# fet_overdrive_v30.net
KiCad netlist of a schematic drawn in EAGLE
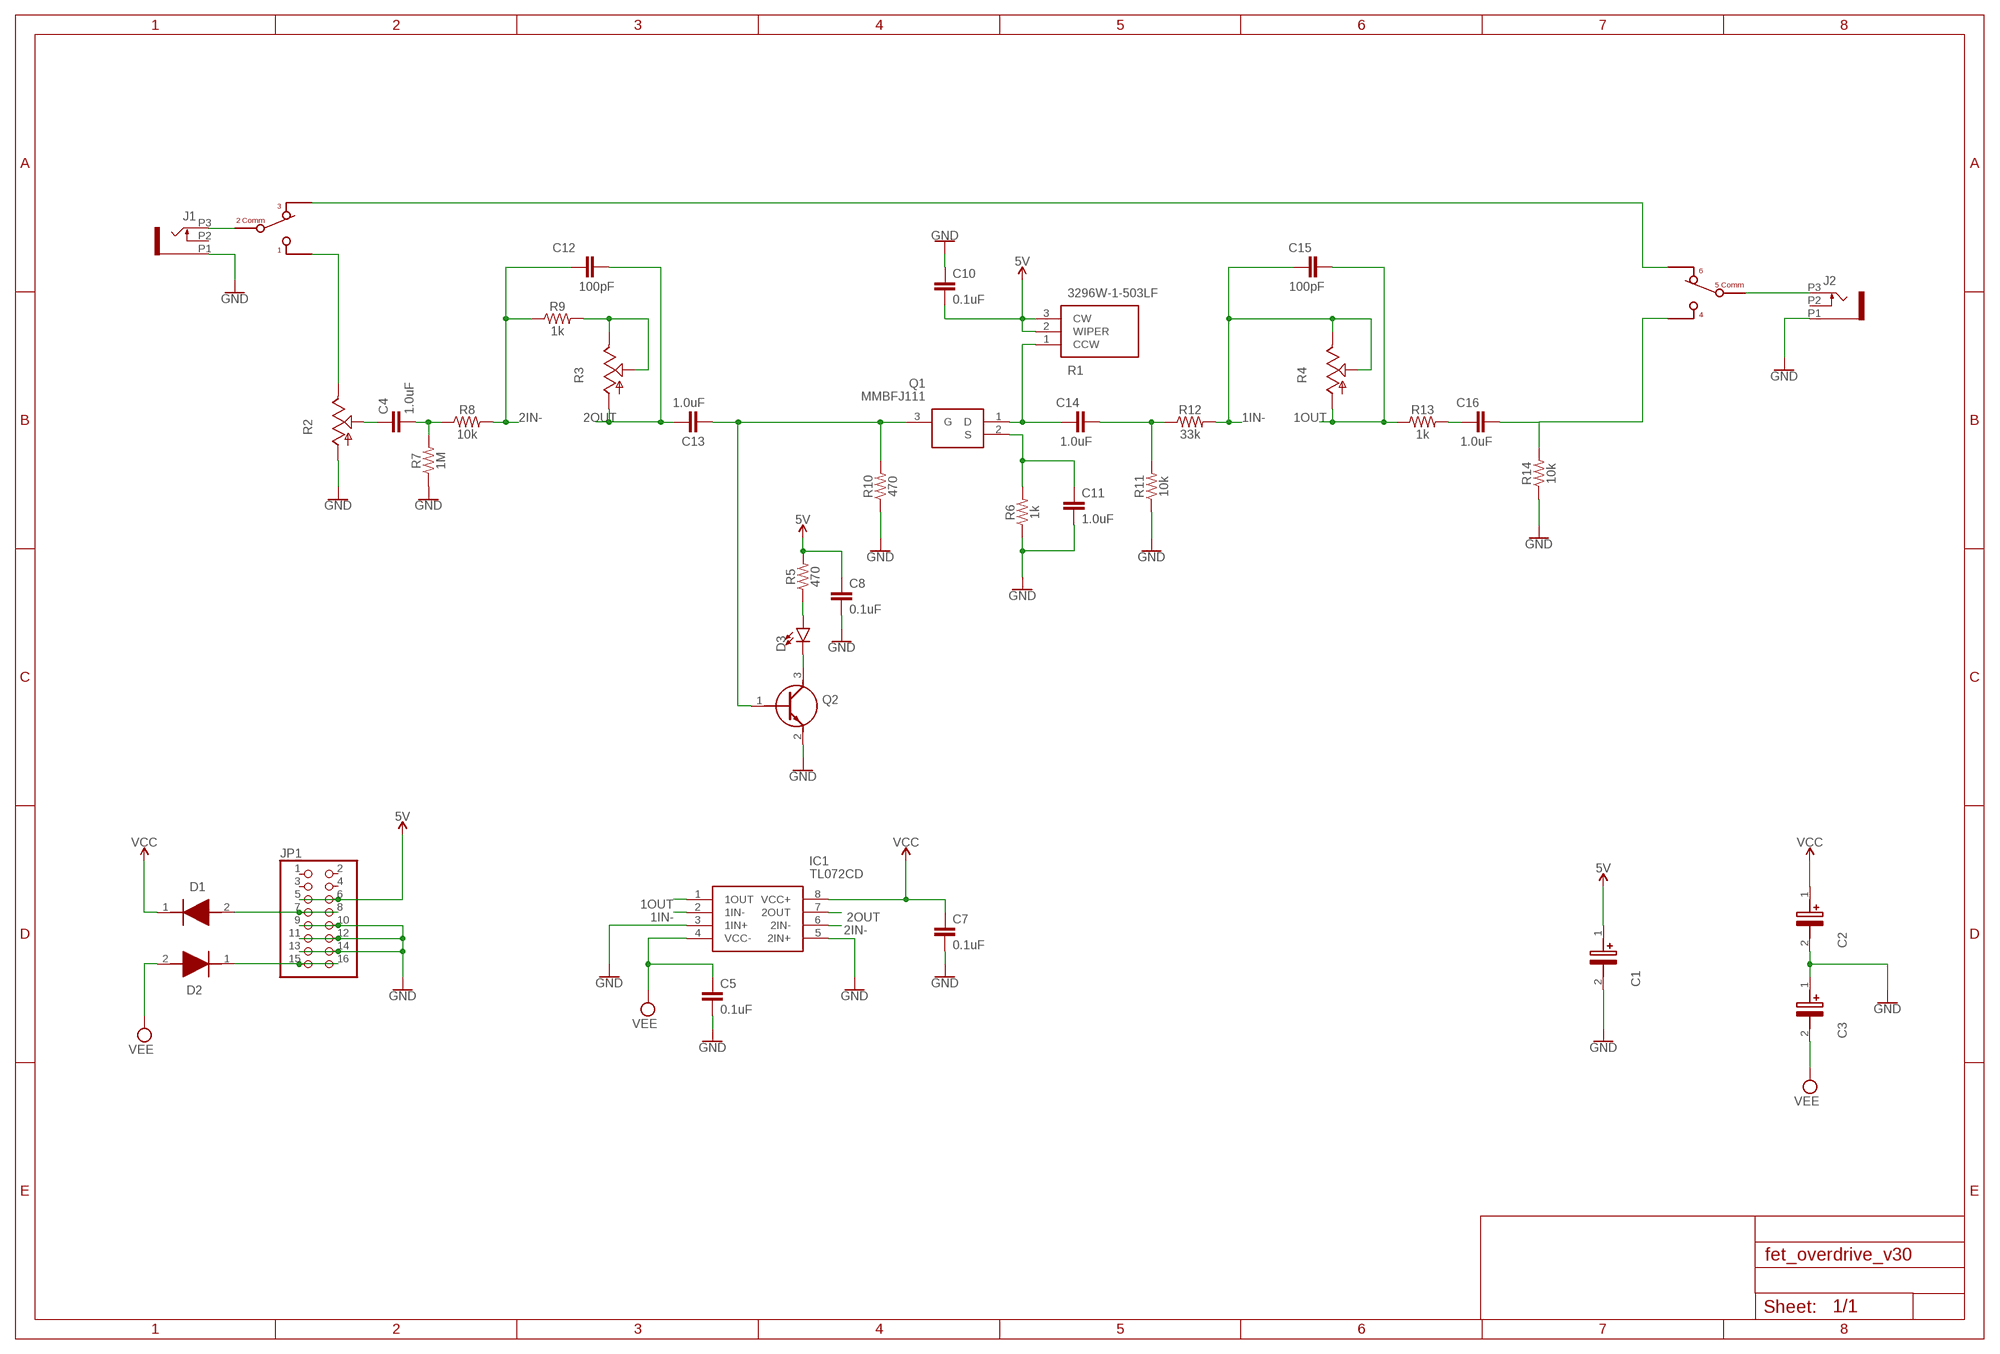
[diagram p0: schematic, sheet 1]

(export (version "E")
  (design (tool "Eeschema 10.0.6"))
  (components
    (comp (ref "C1")
      (value "EEE-FP1E220AR")
      (footprint "eagle-import:EEE0GA101SR")
      (fields (field (name "MOUSER_PART_NUMBER") "667-EEE-FP1E220AR"))
      (libsource (lib "eagle-import") (part "EEE-FP1E220AR"))
    )
    (comp (ref "C2")
      (value "EEE-FK1V470P")
      (footprint "eagle-import:EEE1AA101SP")
      (fields (field (name "MOUSER_PART_NUMBER") "667-EEE-FK1V470P"))
      (libsource (lib "eagle-import") (part "EEE-FK1V470P"))
    )
    (comp (ref "C3")
      (value "EEE-FK1V470P")
      (footprint "eagle-import:EEE1AA101SP")
      (fields (field (name "MOUSER_PART_NUMBER") "667-EEE-FK1V470P"))
      (libsource (lib "eagle-import") (part "EEE-FK1V470P"))
    )
    (comp (ref "C4")
      (value "1.0uF")
      (footprint "eagle-import:0603")
      (libsource (lib "eagle-import") (part "1.0UF-0603-16V-10%"))
    )
    (comp (ref "C5")
      (value "0.1uF")
      (footprint "eagle-import:0603")
      (libsource (lib "eagle-import") (part "0.1UF-0603-25V-5%"))
    )
    (comp (ref "C7")
      (value "0.1uF")
      (footprint "eagle-import:0603")
      (libsource (lib "eagle-import") (part "0.1UF-0603-25V-5%"))
    )
    (comp (ref "C8")
      (value "0.1uF")
      (footprint "eagle-import:0603")
      (libsource (lib "eagle-import") (part "0.1UF-0603-25V-5%"))
    )
    (comp (ref "C10")
      (value "0.1uF")
      (footprint "eagle-import:0603")
      (libsource (lib "eagle-import") (part "0.1UF-0603-25V-5%"))
    )
    (comp (ref "C11")
      (value "1.0uF")
      (footprint "eagle-import:0603")
      (libsource (lib "eagle-import") (part "1.0UF-0603-16V-10%"))
    )
    (comp (ref "C12")
      (value "100pF")
      (footprint "eagle-import:0603")
      (libsource (lib "eagle-import") (part "100PF-0603-50V-5%"))
    )
    (comp (ref "C13")
      (value "1.0uF")
      (footprint "eagle-import:0603")
      (libsource (lib "eagle-import") (part "1.0UF-0603-16V-10%"))
    )
    (comp (ref "C14")
      (value "1.0uF")
      (footprint "eagle-import:0603")
      (libsource (lib "eagle-import") (part "1.0UF-0603-16V-10%"))
    )
    (comp (ref "C15")
      (value "100pF")
      (footprint "eagle-import:0603")
      (libsource (lib "eagle-import") (part "100PF-0603-50V-5%"))
    )
    (comp (ref "C16")
      (value "1.0uF")
      (footprint "eagle-import:0603")
      (libsource (lib "eagle-import") (part "1.0UF-0603-16V-10%"))
    )
    (comp (ref "D1")
      (value "1N5819HW-7-F")
      (footprint "eagle-import:SOD3716X145N")
      (fields (field (name "MOUSER_PART_NUMBER") "621-1N5819HW-F"))
      (libsource (lib "eagle-import") (part "1N5819HW-7-F"))
    )
    (comp (ref "D2")
      (value "1N5819HW-7-F")
      (footprint "eagle-import:SOD3716X145N")
      (fields (field (name "MOUSER_PART_NUMBER") "621-1N5819HW-F"))
      (libsource (lib "eagle-import") (part "1N5819HW-7-F"))
    )
    (comp (ref "D3")
      (value "LED3MM")
      (footprint "eagle-import:LED_3MM")
      (libsource (lib "eagle-import") (part "LED3MM"))
    )
    (comp (ref "IC1")
      (value "TL072CD")
      (footprint "eagle-import:SOIC127P600X175-8N")
      (fields (field (name "MOUSER_PART_NUMBER") "595-TL072CD"))
      (libsource (lib "eagle-import") (part "TL072CD"))
    )
    (comp (ref "J1")
      (value "PJ301_THONKICONN6")
      (footprint "eagle-import:WQP_PJ_301M6")
      (libsource (lib "eagle-import") (part "PJ301_THONKICONN6"))
    )
    (comp (ref "J2")
      (value "PJ301_THONKICONN6")
      (footprint "eagle-import:WQP_PJ_301M6")
      (libsource (lib "eagle-import") (part "PJ301_THONKICONN6"))
    )
    (comp (ref "JP1")
      (value "PINHD-2X8")
      (footprint "eagle-import:2X08")
      (libsource (lib "eagle-import") (part "PINHD-2X8"))
    )
    (comp (ref "Q1")
      (value "MMBFJ111")
      (footprint "eagle-import:SOT96P237X111-3N")
      (fields (field (name "MOUSER_PART_NUMBER") "512-MMBFJ111"))
      (libsource (lib "eagle-import") (part "MMBFJ111"))
    )
    (comp (ref "Q2")
      (value "SMMBT3904LT1G")
      (footprint "eagle-import:SOT96P237X111-3N")
      (fields (field (name "MOUSER_PART_NUMBER") "863-SMMBT3904LT1G"))
      (libsource (lib "eagle-import") (part "SMMBT3904LT1G"))
    )
    (comp (ref "R1")
      (value "3296W-1-503LF")
      (footprint "eagle-import:3296W-1")
      (fields (field (name "MOUSER_PART_NUMBER") "652-3296W-1-503LF"))
      (libsource (lib "eagle-import") (part "3296W-1-503LF"))
    )
    (comp (ref "R2")
      (value "POT_USVERTICAL_PS")
      (footprint "eagle-import:ALPS_POT_VERTICAL_PS")
      (libsource (lib "eagle-import") (part "POT_USVERTICAL_PS"))
    )
    (comp (ref "R3")
      (value "POT_USVERTICAL_PS")
      (footprint "eagle-import:ALPS_POT_VERTICAL_PS")
      (libsource (lib "eagle-import") (part "POT_USVERTICAL_PS"))
    )
    (comp (ref "R4")
      (value "POT_USVERTICAL_PS")
      (footprint "eagle-import:ALPS_POT_VERTICAL_PS")
      (libsource (lib "eagle-import") (part "POT_USVERTICAL_PS"))
    )
    (comp (ref "R5")
      (value "470")
      (footprint "eagle-import:0603")
      (libsource (lib "eagle-import") (part "470OHM-0603-1/10W-1%"))
    )
    (comp (ref "R6")
      (value "1k")
      (footprint "eagle-import:0603")
      (libsource (lib "eagle-import") (part "1KOHM-0603-1/10W-1%"))
    )
    (comp (ref "R7")
      (value "1M")
      (footprint "eagle-import:0603")
      (libsource (lib "eagle-import") (part "1MOHM-0603-1/4W-5%"))
    )
    (comp (ref "R8")
      (value "10k")
      (footprint "eagle-import:0603")
      (libsource (lib "eagle-import") (part "10KOHM-0603-1/10W-1%"))
    )
    (comp (ref "R9")
      (value "1k")
      (footprint "eagle-import:0603")
      (libsource (lib "eagle-import") (part "1KOHM-0603-1/10W-1%"))
    )
    (comp (ref "R10")
      (value "470")
      (footprint "eagle-import:0603")
      (libsource (lib "eagle-import") (part "470OHM-0603-1/10W-1%"))
    )
    (comp (ref "R11")
      (value "10k")
      (footprint "eagle-import:0603")
      (libsource (lib "eagle-import") (part "10KOHM-0603-1/10W-1%"))
    )
    (comp (ref "R12")
      (value "33k")
      (footprint "eagle-import:0603")
      (libsource (lib "eagle-import") (part "33KOHM-0603-1/10W-1%"))
    )
    (comp (ref "R13")
      (value "1k")
      (footprint "eagle-import:0603")
      (libsource (lib "eagle-import") (part "1KOHM-0603-1/10W-1%"))
    )
    (comp (ref "R14")
      (value "10k")
      (footprint "eagle-import:0603")
      (libsource (lib "eagle-import") (part "10KOHM-0603-1/10W-1%"))
    )
    (comp (ref "U$1")
      (value "DAILYWELL-DPDT")
      (footprint "eagle-import:DAILYWELL-DPDT")
      (libsource (lib "eagle-import") (part "DAILYWELL-DPDT"))
    )
  )
  (nets
    (net (code "1") (name "/1IN-") (class "Default")
      (node (ref "C15") (pin "1") (pinfunction "1_1") (pintype "passive"))
      (node (ref "IC1") (pin "2") (pinfunction "1IN-_2") (pintype "bidirectional"))
      (node (ref "R12") (pin "2") (pinfunction "2_2") (pintype "passive"))
      (node (ref "R4") (pin "P$1") (pinfunction "E_P$1") (pintype "passive"))
      (node (ref "R4") (pin "P$2") (pinfunction "S_P$2") (pintype "passive"))
    )
    (net (code "2") (name "/1OUT") (class "Default")
      (node (ref "C15") (pin "2") (pinfunction "2_2") (pintype "passive"))
      (node (ref "IC1") (pin "1") (pinfunction "1OUT_1") (pintype "bidirectional"))
      (node (ref "R13") (pin "1") (pinfunction "1_1") (pintype "passive"))
      (node (ref "R4") (pin "P$3") (pinfunction "A_P$3") (pintype "passive"))
    )
    (net (code "3") (name "/2IN-") (class "Default")
      (node (ref "C12") (pin "1") (pinfunction "1_1") (pintype "passive"))
      (node (ref "IC1") (pin "6") (pinfunction "2IN-_6") (pintype "bidirectional"))
      (node (ref "R8") (pin "2") (pinfunction "2_2") (pintype "passive"))
      (node (ref "R9") (pin "1") (pinfunction "1_1") (pintype "passive"))
    )
    (net (code "4") (name "/2OUT") (class "Default")
      (node (ref "C12") (pin "2") (pinfunction "2_2") (pintype "passive"))
      (node (ref "C13") (pin "1") (pinfunction "1_1") (pintype "passive"))
      (node (ref "IC1") (pin "7") (pinfunction "2OUT_7") (pintype "bidirectional"))
      (node (ref "R3") (pin "P$3") (pinfunction "A_P$3") (pintype "passive"))
    )
    (net (code "5") (name "5V") (class "Default")
      (node (ref "C1") (pin "1") (pinfunction "+_1") (pintype "bidirectional"))
      (node (ref "C10") (pin "2") (pinfunction "2_2") (pintype "passive"))
      (node (ref "C8") (pin "1") (pinfunction "1_1") (pintype "passive"))
      (node (ref "JP1") (pin "5") (pinfunction "5_5") (pintype "passive"))
      (node (ref "JP1") (pin "6") (pinfunction "6_6") (pintype "passive"))
      (node (ref "R1") (pin "2") (pinfunction "WIPER_2") (pintype "bidirectional"))
      (node (ref "R1") (pin "3") (pinfunction "CW_3") (pintype "bidirectional"))
      (node (ref "R5") (pin "2") (pinfunction "2_2") (pintype "passive"))
    )
    (net (code "6") (name "GND") (class "Default")
      (node (ref "C1") (pin "2") (pinfunction "-_2") (pintype "bidirectional"))
      (node (ref "C10") (pin "1") (pinfunction "1_1") (pintype "passive"))
      (node (ref "C11") (pin "2") (pinfunction "2_2") (pintype "passive"))
      (node (ref "C2") (pin "2") (pinfunction "-_2") (pintype "bidirectional"))
      (node (ref "C3") (pin "1") (pinfunction "+_1") (pintype "bidirectional"))
      (node (ref "C5") (pin "2") (pinfunction "2_2") (pintype "passive"))
      (node (ref "C7") (pin "2") (pinfunction "2_2") (pintype "passive"))
      (node (ref "C8") (pin "2") (pinfunction "2_2") (pintype "passive"))
      (node (ref "IC1") (pin "3") (pinfunction "1IN+_3") (pintype "bidirectional"))
      (node (ref "IC1") (pin "5") (pinfunction "2IN+_5") (pintype "bidirectional"))
      (node (ref "J1") (pin "P1") (pinfunction "1_P1") (pintype "passive"))
      (node (ref "J2") (pin "P1") (pinfunction "1_P1") (pintype "passive"))
      (node (ref "JP1") (pin "10") (pinfunction "10_10") (pintype "passive"))
      (node (ref "JP1") (pin "11") (pinfunction "11_11") (pintype "passive"))
      (node (ref "JP1") (pin "12") (pinfunction "12_12") (pintype "passive"))
      (node (ref "JP1") (pin "13") (pinfunction "13_13") (pintype "passive"))
      (node (ref "JP1") (pin "14") (pinfunction "14_14") (pintype "passive"))
      (node (ref "JP1") (pin "9") (pinfunction "9_9") (pintype "passive"))
      (node (ref "Q2") (pin "2") (pinfunction "E_2") (pintype "bidirectional"))
      (node (ref "R10") (pin "1") (pinfunction "1_1") (pintype "passive"))
      (node (ref "R11") (pin "1") (pinfunction "1_1") (pintype "passive"))
      (node (ref "R14") (pin "1") (pinfunction "1_1") (pintype "passive"))
      (node (ref "R2") (pin "P$3") (pinfunction "A_P$3") (pintype "passive"))
      (node (ref "R6") (pin "1") (pinfunction "1_1") (pintype "passive"))
      (node (ref "R7") (pin "1") (pinfunction "1_1") (pintype "passive"))
    )
    (net (code "7") (name "Net-(C4-Pad2)") (class "Default")
      (node (ref "C4") (pin "2") (pinfunction "2_2") (pintype "passive"))
      (node (ref "R7") (pin "2") (pinfunction "2_2") (pintype "passive"))
      (node (ref "R8") (pin "1") (pinfunction "1_1") (pintype "passive"))
    )
    (net (code "8") (name "Net-(C14-Pad2)") (class "Default")
      (node (ref "C14") (pin "2") (pinfunction "2_2") (pintype "passive"))
      (node (ref "R11") (pin "2") (pinfunction "2_2") (pintype "passive"))
      (node (ref "R12") (pin "1") (pinfunction "1_1") (pintype "passive"))
    )
    (net (code "9") (name "Net-(C16-Pad1)") (class "Default")
      (node (ref "C16") (pin "1") (pinfunction "1_1") (pintype "passive"))
      (node (ref "R13") (pin "2") (pinfunction "2_2") (pintype "passive"))
    )
    (net (code "10") (name "Net-(D1-A)") (class "Default")
      (node (ref "D1") (pin "2") (pinfunction "A_2") (pintype "bidirectional"))
      (node (ref "JP1") (pin "7") (pinfunction "7_7") (pintype "passive"))
      (node (ref "JP1") (pin "8") (pinfunction "8_8") (pintype "passive"))
    )
    (net (code "11") (name "Net-(D2-K)") (class "Default")
      (node (ref "D2") (pin "1") (pinfunction "K_1") (pintype "bidirectional"))
      (node (ref "JP1") (pin "15") (pinfunction "15_15") (pintype "passive"))
      (node (ref "JP1") (pin "16") (pinfunction "16_16") (pintype "passive"))
    )
    (net (code "12") (name "Net-(D3-C)") (class "Default")
      (node (ref "D3") (pin "K") (pinfunction "C_K") (pintype "passive"))
      (node (ref "Q2") (pin "3") (pinfunction "C_3") (pintype "bidirectional"))
    )
    (net (code "13") (name "Net-(D3-PadA)") (class "Default")
      (node (ref "D3") (pin "A") (pinfunction "A_A") (pintype "passive"))
      (node (ref "R5") (pin "1") (pinfunction "1_1") (pintype "passive"))
    )
    (net (code "14") (name "Net-(J1-3)") (class "Default")
      (node (ref "J1") (pin "P3") (pinfunction "3_P3") (pintype "passive"))
      (node (ref "U$1") (pin "P$2") (pinfunction "P$2_P$2") (pintype "bidirectional"))
    )
    (net (code "15") (name "Net-(J2-3)") (class "Default")
      (node (ref "J2") (pin "P3") (pinfunction "3_P3") (pintype "passive"))
      (node (ref "U$1") (pin "P$5") (pinfunction "P$2_P$5") (pintype "bidirectional"))
    )
    (net (code "16") (name "Net-(Q1-D)") (class "Default")
      (node (ref "C14") (pin "1") (pinfunction "1_1") (pintype "passive"))
      (node (ref "Q1") (pin "1") (pinfunction "D_1") (pintype "bidirectional"))
      (node (ref "R1") (pin "1") (pinfunction "CCW_1") (pintype "bidirectional"))
    )
    (net (code "17") (name "Net-(Q1-G)") (class "Default")
      (node (ref "C13") (pin "2") (pinfunction "2_2") (pintype "passive"))
      (node (ref "Q1") (pin "3") (pinfunction "G_3") (pintype "bidirectional"))
      (node (ref "Q2") (pin "1") (pinfunction "B_1") (pintype "bidirectional"))
      (node (ref "R10") (pin "2") (pinfunction "2_2") (pintype "passive"))
    )
    (net (code "18") (name "Net-(Q1-S)") (class "Default")
      (node (ref "C11") (pin "1") (pinfunction "1_1") (pintype "passive"))
      (node (ref "Q1") (pin "2") (pinfunction "S_2") (pintype "bidirectional"))
      (node (ref "R6") (pin "2") (pinfunction "2_2") (pintype "passive"))
    )
    (net (code "19") (name "Net-(R2-E)") (class "Default")
      (node (ref "R2") (pin "P$1") (pinfunction "E_P$1") (pintype "passive"))
      (node (ref "U$1") (pin "P$1") (pinfunction "P$1_P$1") (pintype "bidirectional"))
    )
    (net (code "20") (name "Net-(R2-S)") (class "Default")
      (node (ref "C4") (pin "1") (pinfunction "1_1") (pintype "passive"))
      (node (ref "R2") (pin "P$2") (pinfunction "S_P$2") (pintype "passive"))
    )
    (net (code "21") (name "Net-(R3-E)") (class "Default")
      (node (ref "R3") (pin "P$1") (pinfunction "E_P$1") (pintype "passive"))
      (node (ref "R3") (pin "P$2") (pinfunction "S_P$2") (pintype "passive"))
      (node (ref "R9") (pin "2") (pinfunction "2_2") (pintype "passive"))
    )
    (net (code "22") (name "Net-(U$1B-P$1)") (class "Default")
      (node (ref "C16") (pin "2") (pinfunction "2_2") (pintype "passive"))
      (node (ref "R14") (pin "2") (pinfunction "2_2") (pintype "passive"))
      (node (ref "U$1") (pin "P$4") (pinfunction "P$1_P$4") (pintype "bidirectional"))
    )
    (net (code "23") (name "Net-(U$1B-P$3)") (class "Default")
      (node (ref "U$1") (pin "P$3") (pinfunction "P$3_P$3") (pintype "bidirectional"))
      (node (ref "U$1") (pin "P$6") (pinfunction "P$3_P$6") (pintype "bidirectional"))
    )
    (net (code "24") (name "VCC") (class "Default")
      (node (ref "C2") (pin "1") (pinfunction "+_1") (pintype "bidirectional"))
      (node (ref "C7") (pin "1") (pinfunction "1_1") (pintype "passive"))
      (node (ref "D1") (pin "1") (pinfunction "K_1") (pintype "bidirectional"))
      (node (ref "IC1") (pin "8") (pinfunction "VCC+_8") (pintype "bidirectional"))
    )
    (net (code "25") (name "VEE") (class "Default")
      (node (ref "C3") (pin "2") (pinfunction "-_2") (pintype "bidirectional"))
      (node (ref "C5") (pin "1") (pinfunction "1_1") (pintype "passive"))
      (node (ref "D2") (pin "2") (pinfunction "A_2") (pintype "bidirectional"))
      (node (ref "IC1") (pin "4") (pinfunction "VCC-_4") (pintype "bidirectional"))
    )
    (net (code "26") (name "unconnected-(J1-2-PadP2)") (class "Default")
      (node (ref "J1") (pin "P2") (pinfunction "2_P2") (pintype "passive"))
    )
    (net (code "27") (name "unconnected-(J2-2-PadP2)") (class "Default")
      (node (ref "J2") (pin "P2") (pinfunction "2_P2") (pintype "passive"))
    )
    (net (code "28") (name "unconnected-(JP1-Pad1)") (class "Default")
      (node (ref "JP1") (pin "1") (pinfunction "1_1") (pintype "passive"))
    )
    (net (code "29") (name "unconnected-(JP1-Pad2)") (class "Default")
      (node (ref "JP1") (pin "2") (pinfunction "2_2") (pintype "passive"))
    )
    (net (code "30") (name "unconnected-(JP1-Pad3)") (class "Default")
      (node (ref "JP1") (pin "3") (pinfunction "3_3") (pintype "passive"))
    )
    (net (code "31") (name "unconnected-(JP1-Pad4)") (class "Default")
      (node (ref "JP1") (pin "4") (pinfunction "4_4") (pintype "passive"))
    )
  )
)
